# garage_door_remote.net
KiCad netlist of a schematic drawn in EAGLE
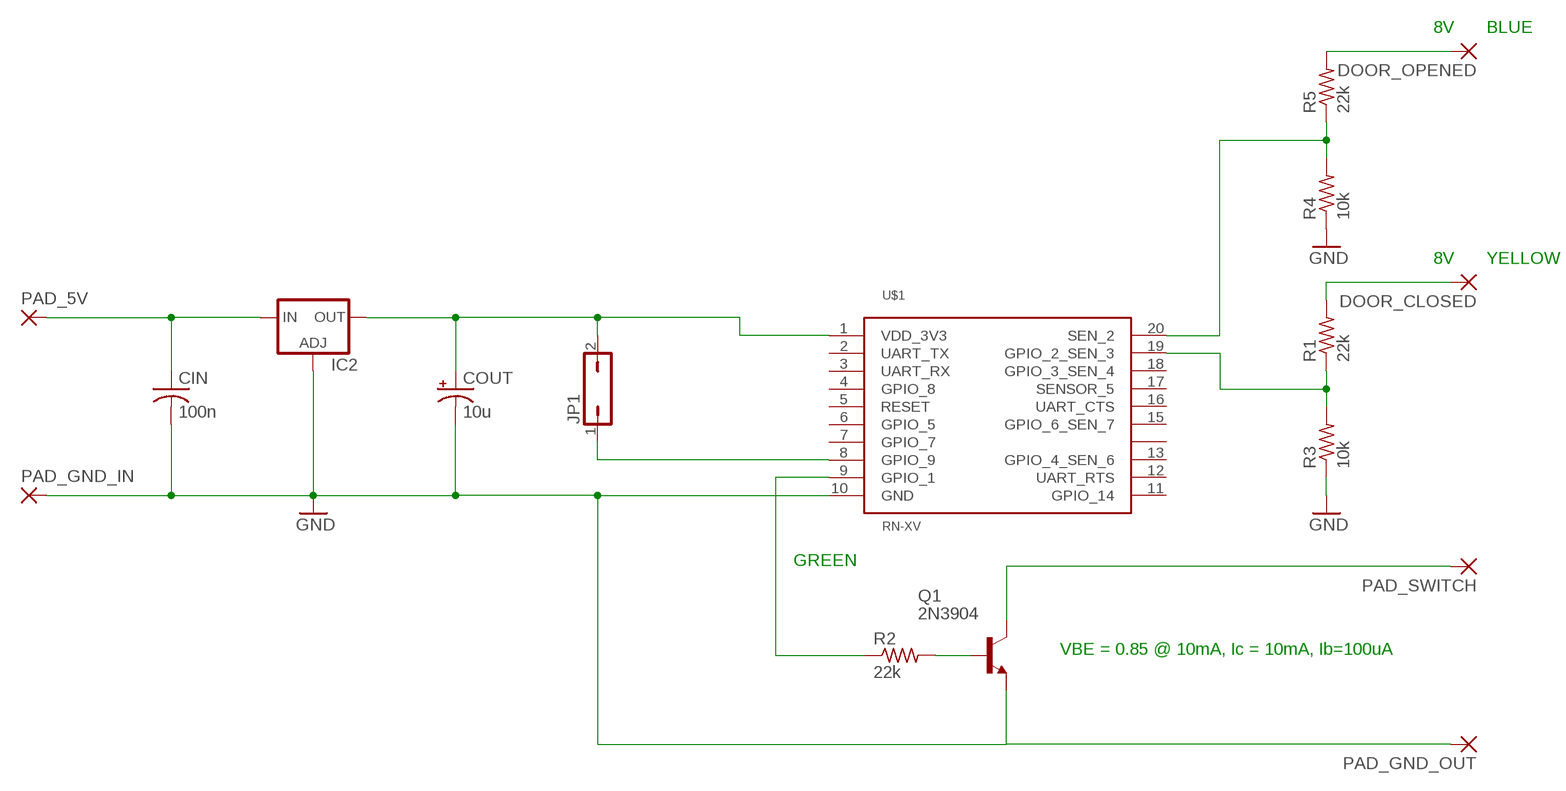
[diagram p0: schematic, sheet 1]

(export (version "E")
  (design (tool "Eeschema 10.0.6"))
  (components
    (comp (ref "CIN")
      (value "100n")
      (footprint "eagle-import:C025-024X044")
      (libsource (lib "eagle-import") (part "C-US025-024X044"))
    )
    (comp (ref "COUT")
      (value "10u")
      (footprint "eagle-import:E2,5-6E")
      (libsource (lib "eagle-import") (part "CPOL-USE2,5-6E"))
    )
    (comp (ref "DOOR_CLOSED")
      (value "2,54/1,0")
      (footprint "eagle-import:2,54_1,0")
      (libsource (lib "eagle-import") (part "2,54/1,0"))
    )
    (comp (ref "DOOR_OPENED")
      (value "2,54/1,0")
      (footprint "eagle-import:2,54_1,0")
      (libsource (lib "eagle-import") (part "2,54/1,0"))
    )
    (comp (ref "IC2")
      (value "LM317TS")
      (footprint "eagle-import:317TS")
      (libsource (lib "eagle-import") (part "LM317TS"))
    )
    (comp (ref "JP1")
      (value "JP1Q")
      (footprint "eagle-import:JP1")
      (libsource (lib "eagle-import") (part "JP1Q"))
    )
    (comp (ref "PAD_5V")
      (value "2,54/1,0")
      (footprint "eagle-import:2,54_1,0")
      (libsource (lib "eagle-import") (part "2,54/1,0"))
    )
    (comp (ref "PAD_GND_IN")
      (value "2,54/1,0")
      (footprint "eagle-import:2,54_1,0")
      (libsource (lib "eagle-import") (part "2,54/1,0"))
    )
    (comp (ref "PAD_GND_OUT")
      (value "2,54/1,0")
      (footprint "eagle-import:2,54_1,0")
      (libsource (lib "eagle-import") (part "2,54/1,0"))
    )
    (comp (ref "PAD_SWITCH")
      (value "2,54/1,0")
      (footprint "eagle-import:2,54_1,0")
      (libsource (lib "eagle-import") (part "2,54/1,0"))
    )
    (comp (ref "Q1")
      (value "2N3904")
      (footprint "eagle-import:TO92")
      (libsource (lib "eagle-import") (part "2N3904"))
    )
    (comp (ref "R1")
      (value "22k")
      (footprint "eagle-import:0207_12")
      (libsource (lib "eagle-import") (part "R-US_0207/12"))
    )
    (comp (ref "R2")
      (value "22k")
      (footprint "eagle-import:0207_12")
      (libsource (lib "eagle-import") (part "R-US_0207/12"))
    )
    (comp (ref "R3")
      (value "10k")
      (footprint "eagle-import:0207_12")
      (libsource (lib "eagle-import") (part "R-US_0207/12"))
    )
    (comp (ref "R4")
      (value "10k")
      (footprint "eagle-import:0204V")
      (libsource (lib "eagle-import") (part "R-US_0204/2V"))
    )
    (comp (ref "R5")
      (value "22k")
      (footprint "eagle-import:0204V")
      (libsource (lib "eagle-import") (part "R-US_0204/2V"))
    )
    (comp (ref "U$1")
      (value "RN-XV")
      (footprint "eagle-import:RN-XV")
      (libsource (lib "eagle-import") (part "RN-XV"))
    )
  )
  (nets
    (net (code "1") (name "GND") (class "Default")
      (node (ref "CIN") (pin "2") (pinfunction "2_2") (pintype "passive"))
      (node (ref "COUT") (pin "-") (pinfunction "-_-") (pintype "passive"))
      (node (ref "IC2") (pin "1") (pinfunction "ADJ_1") (pintype "input"))
      (node (ref "PAD_GND_IN") (pin "1") (pinfunction "P_1") (pintype "passive"))
      (node (ref "PAD_GND_OUT") (pin "1") (pinfunction "P_1") (pintype "passive"))
      (node (ref "Q1") (pin "3") (pinfunction "E_3") (pintype "passive"))
      (node (ref "R3") (pin "1") (pinfunction "1_1") (pintype "passive"))
      (node (ref "R4") (pin "1") (pinfunction "1_1") (pintype "passive"))
      (node (ref "U$1") (pin "10") (pinfunction "GND_10") (pintype "power_in"))
    )
    (net (code "2") (name "Net-(DOOR_CLOSED-P)") (class "Default")
      (node (ref "DOOR_CLOSED") (pin "1") (pinfunction "P_1") (pintype "passive"))
      (node (ref "R1") (pin "2") (pinfunction "2_2") (pintype "passive"))
    )
    (net (code "3") (name "Net-(DOOR_OPENED-P)") (class "Default")
      (node (ref "DOOR_OPENED") (pin "1") (pinfunction "P_1") (pintype "passive"))
      (node (ref "R5") (pin "2") (pinfunction "2_2") (pintype "passive"))
    )
    (net (code "4") (name "Net-(IC2-IN)") (class "Default")
      (node (ref "CIN") (pin "1") (pinfunction "1_1") (pintype "passive"))
      (node (ref "IC2") (pin "3") (pinfunction "IN_3") (pintype "input"))
      (node (ref "PAD_5V") (pin "1") (pinfunction "P_1") (pintype "passive"))
    )
    (net (code "5") (name "Net-(IC2-OUT)") (class "Default")
      (node (ref "COUT") (pin "+") (pinfunction "+_+") (pintype "passive"))
      (node (ref "IC2") (pin "2") (pinfunction "OUT_2") (pintype "passive"))
      (node (ref "JP1") (pin "2") (pinfunction "2_2") (pintype "passive"))
      (node (ref "U$1") (pin "1") (pinfunction "VDD_3V3_1") (pintype "power_in"))
    )
    (net (code "6") (name "Net-(PAD_SWITCH-P)") (class "Default")
      (node (ref "PAD_SWITCH") (pin "1") (pinfunction "P_1") (pintype "passive"))
      (node (ref "Q1") (pin "1") (pinfunction "C_1") (pintype "passive"))
    )
    (net (code "7") (name "Net-(Q1-B)") (class "Default")
      (node (ref "Q1") (pin "2") (pinfunction "B_2") (pintype "passive"))
      (node (ref "R2") (pin "2") (pinfunction "2_2") (pintype "passive"))
    )
    (net (code "8") (name "Net-(U$1-GPIO_1)") (class "Default")
      (node (ref "R2") (pin "1") (pinfunction "1_1") (pintype "passive"))
      (node (ref "U$1") (pin "9") (pinfunction "GPIO_1_9") (pintype "bidirectional"))
    )
    (net (code "9") (name "Net-(U$1-GPIO_2_SEN_3)") (class "Default")
      (node (ref "R1") (pin "1") (pinfunction "1_1") (pintype "passive"))
      (node (ref "R3") (pin "2") (pinfunction "2_2") (pintype "passive"))
      (node (ref "U$1") (pin "19") (pinfunction "GPIO_2_SEN_3_19") (pintype "bidirectional"))
    )
    (net (code "10") (name "Net-(U$1-GPIO_9)") (class "Default")
      (node (ref "JP1") (pin "1") (pinfunction "1_1") (pintype "passive"))
      (node (ref "U$1") (pin "8") (pinfunction "GPIO_9_8") (pintype "bidirectional"))
    )
    (net (code "11") (name "Net-(U$1-SEN_2)") (class "Default")
      (node (ref "R4") (pin "2") (pinfunction "2_2") (pintype "passive"))
      (node (ref "R5") (pin "1") (pinfunction "1_1") (pintype "passive"))
      (node (ref "U$1") (pin "20") (pinfunction "SEN_2_20") (pintype "input"))
    )
    (net (code "12") (name "unconnected-(U$1-GPIO_3_SEN_4-Pad18)") (class "Default")
      (node (ref "U$1") (pin "18") (pinfunction "GPIO_3_SEN_4_18") (pintype "bidirectional"))
    )
    (net (code "13") (name "unconnected-(U$1-GPIO_4_SEN_6-Pad13)") (class "Default")
      (node (ref "U$1") (pin "13") (pinfunction "GPIO_4_SEN_6_13") (pintype "bidirectional"))
    )
    (net (code "14") (name "unconnected-(U$1-GPIO_5-Pad6)") (class "Default")
      (node (ref "U$1") (pin "6") (pinfunction "GPIO_5_6") (pintype "bidirectional"))
    )
    (net (code "15") (name "unconnected-(U$1-GPIO_6_SEN_7-Pad15)") (class "Default")
      (node (ref "U$1") (pin "15") (pinfunction "GPIO_6_SEN_7_15") (pintype "bidirectional"))
    )
    (net (code "16") (name "unconnected-(U$1-GPIO_7-Pad7)") (class "Default")
      (node (ref "U$1") (pin "7") (pinfunction "GPIO_7_7") (pintype "bidirectional"))
    )
    (net (code "17") (name "unconnected-(U$1-GPIO_8-Pad4)") (class "Default")
      (node (ref "U$1") (pin "4") (pinfunction "GPIO_8_4") (pintype "bidirectional"))
    )
    (net (code "18") (name "unconnected-(U$1-GPIO_14-Pad11)") (class "Default")
      (node (ref "U$1") (pin "11") (pinfunction "GPIO_14_11") (pintype "bidirectional"))
    )
    (net (code "19") (name "unconnected-(U$1-NOT_USED-Pad14)") (class "Default")
      (node (ref "U$1") (pin "14") (pinfunction "NOT_USED_14") (pintype "no_connect"))
    )
    (net (code "20") (name "unconnected-(U$1-RESET-Pad5)") (class "Default")
      (node (ref "U$1") (pin "5") (pinfunction "RESET_5") (pintype "input"))
    )
    (net (code "21") (name "unconnected-(U$1-SENSOR_5-Pad17)") (class "Default")
      (node (ref "U$1") (pin "17") (pinfunction "SENSOR_5_17") (pintype "input"))
    )
    (net (code "22") (name "unconnected-(U$1-UART_CTS-Pad16)") (class "Default")
      (node (ref "U$1") (pin "16") (pinfunction "UART_CTS_16") (pintype "input"))
    )
    (net (code "23") (name "unconnected-(U$1-UART_RTS-Pad12)") (class "Default")
      (node (ref "U$1") (pin "12") (pinfunction "UART_RTS_12") (pintype "output"))
    )
    (net (code "24") (name "unconnected-(U$1-UART_RX-Pad3)") (class "Default")
      (node (ref "U$1") (pin "3") (pinfunction "UART_RX_3") (pintype "input"))
    )
    (net (code "25") (name "unconnected-(U$1-UART_TX-Pad2)") (class "Default")
      (node (ref "U$1") (pin "2") (pinfunction "UART_TX_2") (pintype "output"))
    )
  )
)
